# ADC.net
KiCad netlist of a schematic drawn in Altium Designer
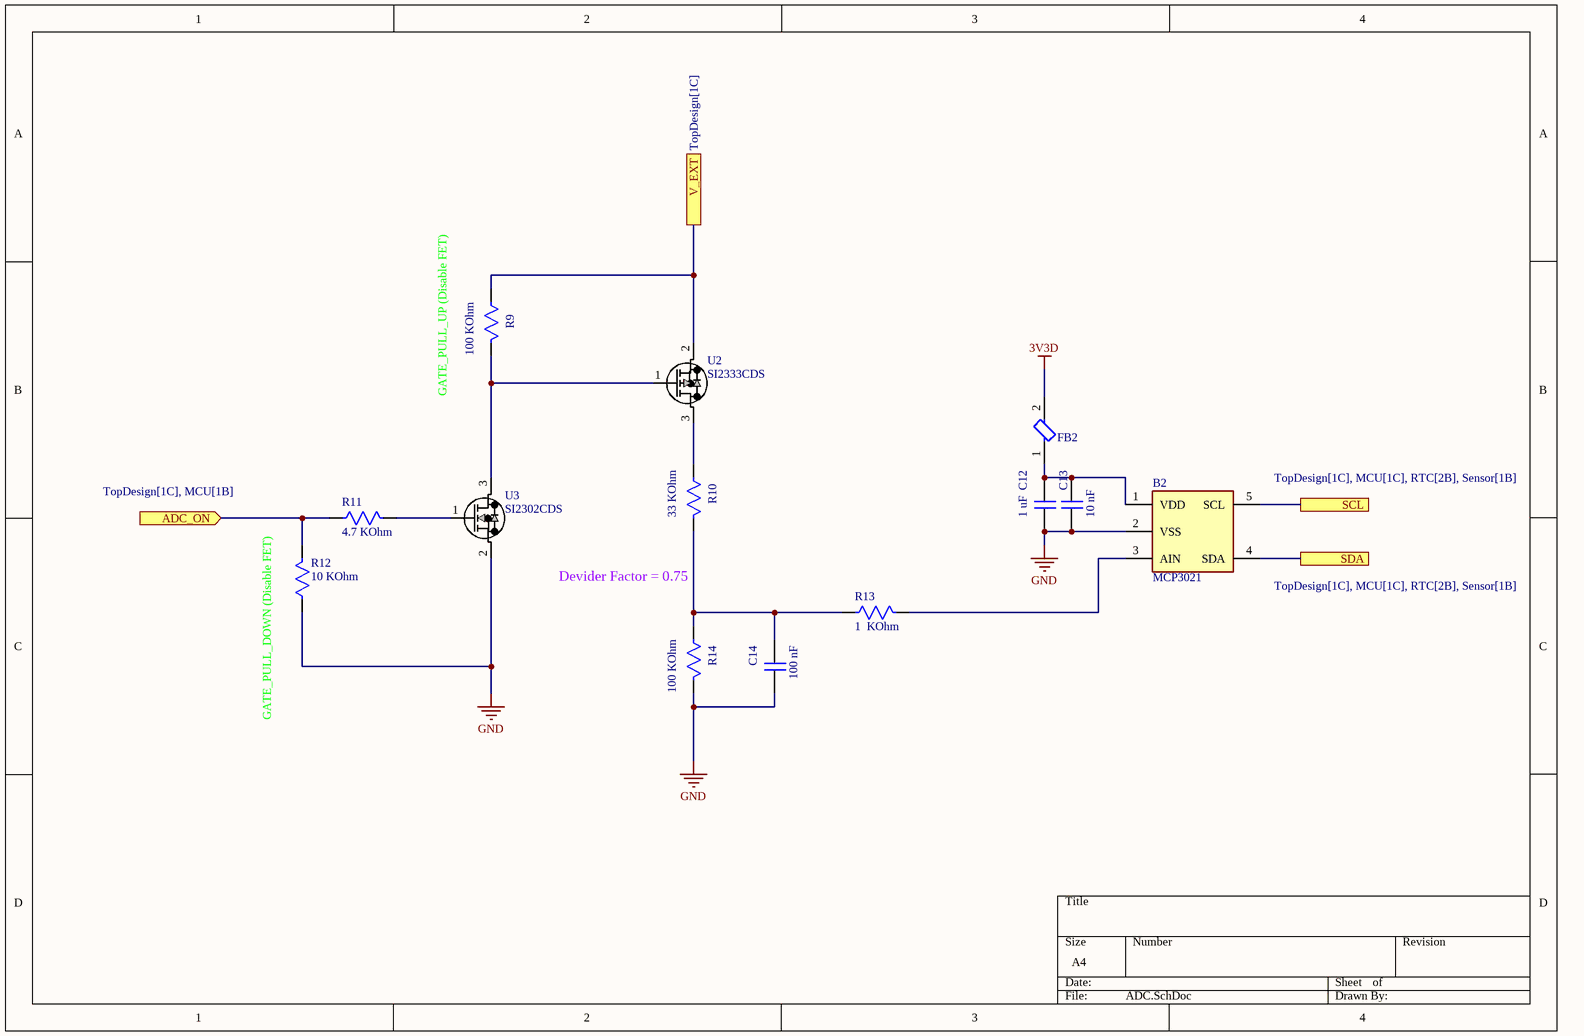
[diagram p0: ADC.SchDoc]

(export (version "E")
  (design (tool "Eeschema 10.0.6"))
  (components
    (comp (ref "B2")
      (value "MCP3021")
      (footprint "MCP3021A5T-E_OT")
      (description "ADC - ,SAR, Single Ended ,10-bit ,I2C , 250uA-Active ,1uA -Standby")
      (fields (field (name "MANUFACTURER_PART_NUMBER") "MCP3021A5T-E/OT"))
      (libsource (lib "Aptinex_devices") (part "MCP3021A5T-E_OT"))
    )
    (comp (ref "C12")
      (value "1 uF")
      (footprint "CAP_0603")
      (description "Cap SMD.")
      (libsource (lib "Aptinex_discrete") (part "Cap SMD"))
    )
    (comp (ref "C13")
      (value "10 nF")
      (footprint "CAP_0603")
      (description "Cap SMD.")
      (libsource (lib "Aptinex_discrete") (part "Cap SMD"))
    )
    (comp (ref "C14")
      (value "100 nF")
      (footprint "CAP_0603")
      (description "Cap SMD.")
      (libsource (lib "Aptinex_discrete") (part "Cap SMD"))
    )
    (comp (ref "FB2")
      (value "BLM18KG601SN1D")
      (footprint "FBead_Murata_BLM18KG601SN1D")
      (libsource (lib "Aptinex_discrete") (part "BLM18KG601SN1D"))
    )
    (comp (ref "R9")
      (value "100 KOhm")
      (footprint "Res_0603")
      (description "SMD Resistor")
      (fields (field (name "MP") "RC0805FR-07330RL") (field (name "MF") "Yageo"))
      (libsource (lib "Aptinex_discrete") (part "Res smd"))
    )
    (comp (ref "R10")
      (value "33 KOhm")
      (footprint "Res_0603")
      (description "SMD Resistor")
      (fields (field (name "MP") "RC0805FR-07330RL") (field (name "MF") "Yageo"))
      (libsource (lib "Aptinex_discrete") (part "Res smd"))
    )
    (comp (ref "R11")
      (value "4.7 KOhm")
      (footprint "Res_0603")
      (description "SMD Resistor")
      (fields (field (name "MP") "RC0805FR-07330RL") (field (name "MF") "Yageo"))
      (libsource (lib "Aptinex_discrete") (part "Res smd"))
    )
    (comp (ref "R12")
      (value "10 KOhm")
      (footprint "Res_0603")
      (description "SMD Resistor")
      (fields (field (name "MP") "RC0805FR-07330RL") (field (name "MF") "Yageo"))
      (libsource (lib "Aptinex_discrete") (part "Res smd"))
    )
    (comp (ref "R13")
      (value "1  KOhm")
      (footprint "Res_0603")
      (description "SMD Resistor")
      (fields (field (name "MP") "RC0805FR-07330RL") (field (name "MF") "Yageo"))
      (libsource (lib "Aptinex_discrete") (part "Res smd"))
    )
    (comp (ref "R14")
      (value "100 KOhm")
      (footprint "Res_0603")
      (description "SMD Resistor")
      (fields (field (name "MP") "RC0805FR-07330RL") (field (name "MF") "Yageo"))
      (libsource (lib "Aptinex_discrete") (part "Res smd"))
    )
    (comp (ref "U2")
      (value "SI2333CDS")
      (footprint "SOT-23")
      (description "P-Channel  MOSFET Vds=12V ,RDS(on)=35mOhm .  at VGS = 4.5 V")
      (libsource (lib "Aptinex_discrete") (part "SI2333CDS"))
    )
    (comp (ref "U3")
      (value "SI2302CDS")
      (footprint "SOT-23")
      (description "N-Channel  MOSFET Vds=20V ,RDS(on)=57mOhm .  at VGS = 4.5 V")
      (libsource (lib "Aptinex_discrete") (part "SI2302CDS"))
    )
  )
  (nets
    (net (code "1") (name "/ADC_ON") (class "Default")
      (node (ref "R11") (pin "2") (pinfunction "2_2") (pintype "passive"))
      (node (ref "R12") (pin "1") (pinfunction "1_1") (pintype "passive"))
    )
    (net (code "2") (name "/SCL") (class "Default")
      (node (ref "B2") (pin "5") (pinfunction "SCL_5") (pintype "passive"))
    )
    (net (code "3") (name "/SDA") (class "Default")
      (node (ref "B2") (pin "4") (pinfunction "SDA_4") (pintype "passive"))
    )
    (net (code "4") (name "/V_EXT") (class "Default")
      (node (ref "R9") (pin "2") (pinfunction "2_2") (pintype "passive"))
      (node (ref "U2") (pin "2") (pinfunction "S_2") (pintype "passive"))
    )
    (net (code "5") (name "3V3D") (class "Default")
      (node (ref "FB2") (pin "2") (pinfunction "2_2") (pintype "passive"))
    )
    (net (code "6") (name "GND") (class "Default")
      (node (ref "B2") (pin "2") (pinfunction "VSS_2") (pintype "passive"))
      (node (ref "C12") (pin "1") (pinfunction "1_1") (pintype "passive"))
      (node (ref "C13") (pin "1") (pinfunction "1_1") (pintype "passive"))
      (node (ref "C14") (pin "1") (pinfunction "1_1") (pintype "passive"))
      (node (ref "R12") (pin "2") (pinfunction "2_2") (pintype "passive"))
      (node (ref "R14") (pin "1") (pinfunction "1_1") (pintype "passive"))
      (node (ref "U3") (pin "2") (pinfunction "S_2") (pintype "passive"))
    )
    (net (code "7") (name "Net-(B2-AIN)") (class "Default")
      (node (ref "B2") (pin "3") (pinfunction "AIN_3") (pintype "passive"))
      (node (ref "R13") (pin "1") (pinfunction "1_1") (pintype "passive"))
    )
    (net (code "8") (name "Net-(B2-VDD)") (class "Default")
      (node (ref "B2") (pin "1") (pinfunction "VDD_1") (pintype "passive"))
      (node (ref "C12") (pin "2") (pinfunction "2_2") (pintype "passive"))
      (node (ref "C13") (pin "2") (pinfunction "2_2") (pintype "passive"))
      (node (ref "FB2") (pin "1") (pinfunction "1_1") (pintype "passive"))
    )
    (net (code "9") (name "Net-(C14-Pad2)") (class "Default")
      (node (ref "C14") (pin "2") (pinfunction "2_2") (pintype "passive"))
      (node (ref "R10") (pin "1") (pinfunction "1_1") (pintype "passive"))
      (node (ref "R13") (pin "2") (pinfunction "2_2") (pintype "passive"))
      (node (ref "R14") (pin "2") (pinfunction "2_2") (pintype "passive"))
    )
    (net (code "10") (name "Net-(U2-D)") (class "Default")
      (node (ref "R10") (pin "2") (pinfunction "2_2") (pintype "passive"))
      (node (ref "U2") (pin "3") (pinfunction "D_3") (pintype "passive"))
    )
    (net (code "11") (name "Net-(U2-G)") (class "Default")
      (node (ref "R9") (pin "1") (pinfunction "1_1") (pintype "passive"))
      (node (ref "U2") (pin "1") (pinfunction "G_1") (pintype "passive"))
      (node (ref "U3") (pin "3") (pinfunction "D_3") (pintype "passive"))
    )
    (net (code "12") (name "Net-(U3-G)") (class "Default")
      (node (ref "R11") (pin "1") (pinfunction "1_1") (pintype "passive"))
      (node (ref "U3") (pin "1") (pinfunction "G_1") (pintype "passive"))
    )
  )
)
